# avr3.net
KiCad netlist of a schematic drawn in EAGLE
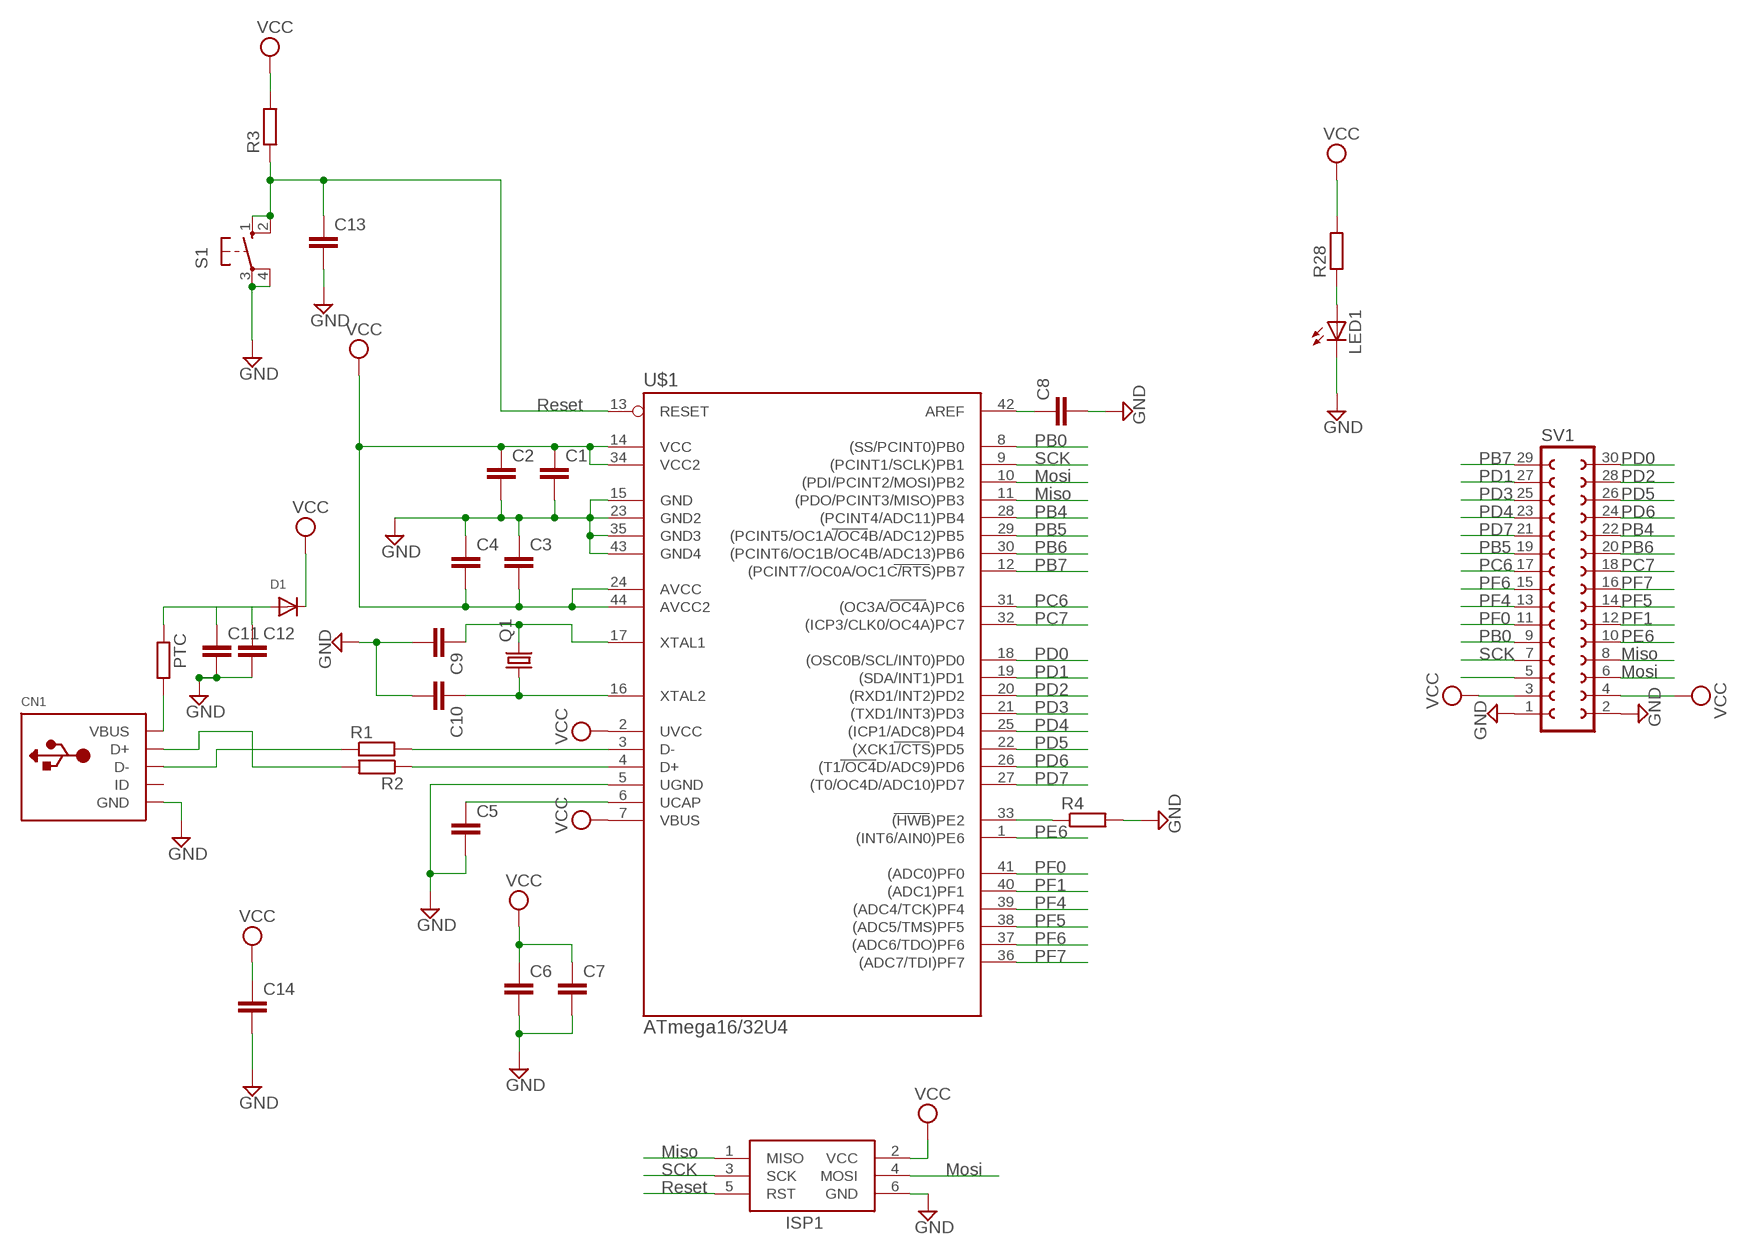
[diagram p0: schematic, sheet 1]

(export (version "E")
  (design (tool "Eeschema 10.0.6"))
  (components
    (comp (ref "C1")
      (value "C-EUC1206")
      (footprint "eagle-import:C1206")
      (libsource (lib "eagle-import") (part "C-EUC1206"))
    )
    (comp (ref "C2")
      (value "C-EUC1206")
      (footprint "eagle-import:C1206")
      (libsource (lib "eagle-import") (part "C-EUC1206"))
    )
    (comp (ref "C3")
      (value "C-EUC1206")
      (footprint "eagle-import:C1206")
      (libsource (lib "eagle-import") (part "C-EUC1206"))
    )
    (comp (ref "C4")
      (value "C-EUC1206")
      (footprint "eagle-import:C1206")
      (libsource (lib "eagle-import") (part "C-EUC1206"))
    )
    (comp (ref "C5")
      (value "C-EUC1206")
      (footprint "eagle-import:C1206")
      (libsource (lib "eagle-import") (part "C-EUC1206"))
    )
    (comp (ref "C6")
      (value "C-EUC1206")
      (footprint "eagle-import:C1206")
      (libsource (lib "eagle-import") (part "C-EUC1206"))
    )
    (comp (ref "C7")
      (value "C-EUC1206")
      (footprint "eagle-import:C1206")
      (libsource (lib "eagle-import") (part "C-EUC1206"))
    )
    (comp (ref "C8")
      (value "C-EUC1206")
      (footprint "eagle-import:C1206")
      (libsource (lib "eagle-import") (part "C-EUC1206"))
    )
    (comp (ref "C9")
      (value "C-EUC1206")
      (footprint "eagle-import:C1206")
      (libsource (lib "eagle-import") (part "C-EUC1206"))
    )
    (comp (ref "C10")
      (value "C-EUC1206")
      (footprint "eagle-import:C1206")
      (libsource (lib "eagle-import") (part "C-EUC1206"))
    )
    (comp (ref "C11")
      (value "C-EUC1206")
      (footprint "eagle-import:C1206")
      (libsource (lib "eagle-import") (part "C-EUC1206"))
    )
    (comp (ref "C12")
      (value "C-EUC1206")
      (footprint "eagle-import:C1206")
      (libsource (lib "eagle-import") (part "C-EUC1206"))
    )
    (comp (ref "C13")
      (value "C-EUC1206")
      (footprint "eagle-import:C1206")
      (libsource (lib "eagle-import") (part "C-EUC1206"))
    )
    (comp (ref "C14")
      (value "C-EUC1206")
      (footprint "eagle-import:C1206")
      (libsource (lib "eagle-import") (part "C-EUC1206"))
    )
    (comp (ref "CN1")
      (value "USBMINIB")
      (footprint "eagle-import:USB-MINIB")
      (libsource (lib "eagle-import") (part "USBMINIB"))
    )
    (comp (ref "D1")
      (value "DIODESOD-123")
      (footprint "eagle-import:SOD-123")
      (libsource (lib "eagle-import") (part "DIODESOD-123"))
    )
    (comp (ref "ISP1")
      (value "AVRISP-6")
      (footprint "eagle-import:AVRISP")
      (libsource (lib "eagle-import") (part "AVRISP-6"))
    )
    (comp (ref "LED1")
      (value "LEDCHIPLED_1206")
      (footprint "eagle-import:CHIPLED_1206")
      (libsource (lib "eagle-import") (part "LEDCHIPLED_1206"))
    )
    (comp (ref "PTC")
      (value "R-EU_R1206")
      (footprint "eagle-import:R1206")
      (libsource (lib "eagle-import") (part "R-EU_R1206"))
    )
    (comp (ref "Q1")
      (value "CRYSTALHC49UP")
      (footprint "eagle-import:HC49UP")
      (fields (field (name "OC_FARNELL") "unknown") (field (name "OC_NEWARK") "unknown"))
      (libsource (lib "eagle-import") (part "CRYSTALHC49UP"))
    )
    (comp (ref "R1")
      (value "R-EU_R1206")
      (footprint "eagle-import:R1206")
      (libsource (lib "eagle-import") (part "R-EU_R1206"))
    )
    (comp (ref "R2")
      (value "R-EU_R1206")
      (footprint "eagle-import:R1206")
      (libsource (lib "eagle-import") (part "R-EU_R1206"))
    )
    (comp (ref "R3")
      (value "R-EU_R1206")
      (footprint "eagle-import:R1206")
      (libsource (lib "eagle-import") (part "R-EU_R1206"))
    )
    (comp (ref "R4")
      (value "R-EU_R1206")
      (footprint "eagle-import:R1206")
      (libsource (lib "eagle-import") (part "R-EU_R1206"))
    )
    (comp (ref "R28")
      (value "R-EU_R1206")
      (footprint "eagle-import:R1206")
      (libsource (lib "eagle-import") (part "R-EU_R1206"))
    )
    (comp (ref "S1")
      (value "10-XX")
      (footprint "eagle-import:B3F-10XX")
      (fields (field (name "MPN") "B3F-1000"))
      (libsource (lib "eagle-import") (part "10-XX"))
    )
    (comp (ref "SV1")
      (value "FE15-2")
      (footprint "eagle-import:FE15-2")
      (libsource (lib "eagle-import") (part "FE15-2"))
    )
    (comp (ref "U$1")
      (value "ATmega16/32U4")
      (footprint "eagle-import:TQFP44")
      (libsource (lib "eagle-import") (part "ATMEGA32U4-AU"))
    )
  )
  (nets
    (net (code "1") (name "/MISO") (class "Default")
      (node (ref "ISP1") (pin "1") (pinfunction "MISO_1") (pintype "input"))
      (node (ref "SV1") (pin "8") (pinfunction "8_8") (pintype "passive"))
      (node (ref "U$1") (pin "11") (pinfunction "(PDO/PCINT3/MISO)PB3_11") (pintype "bidirectional"))
    )
    (net (code "2") (name "/MOSI") (class "Default")
      (node (ref "ISP1") (pin "4") (pinfunction "MOSI_4") (pintype "output"))
      (node (ref "SV1") (pin "6") (pinfunction "6_6") (pintype "passive"))
      (node (ref "U$1") (pin "10") (pinfunction "(PDI/PCINT2/MOSI)PB2_10") (pintype "bidirectional"))
    )
    (net (code "3") (name "/PB0") (class "Default")
      (node (ref "SV1") (pin "9") (pinfunction "9_9") (pintype "passive"))
      (node (ref "U$1") (pin "8") (pinfunction "(SS/PCINT0)PB0_8") (pintype "bidirectional"))
    )
    (net (code "4") (name "/PB4") (class "Default")
      (node (ref "SV1") (pin "22") (pinfunction "22_22") (pintype "passive"))
      (node (ref "U$1") (pin "28") (pinfunction "(PCINT4/ADC11)PB4_28") (pintype "bidirectional"))
    )
    (net (code "5") (name "/PB5") (class "Default")
      (node (ref "SV1") (pin "19") (pinfunction "19_19") (pintype "passive"))
      (node (ref "U$1") (pin "29") (pinfunction "(PCINT5/OC1A/OC4B/ADC12)PB5_29") (pintype "bidirectional"))
    )
    (net (code "6") (name "/PB6") (class "Default")
      (node (ref "SV1") (pin "20") (pinfunction "20_20") (pintype "passive"))
      (node (ref "U$1") (pin "30") (pinfunction "(PCINT6/OC1B/OC4B/ADC13)PB6_30") (pintype "bidirectional"))
    )
    (net (code "7") (name "/PB7") (class "Default")
      (node (ref "SV1") (pin "29") (pinfunction "29_29") (pintype "passive"))
      (node (ref "U$1") (pin "12") (pinfunction "(PCINT7/OC0A/OC1C/RTS)PB7_12") (pintype "bidirectional"))
    )
    (net (code "8") (name "/PC6") (class "Default")
      (node (ref "SV1") (pin "17") (pinfunction "17_17") (pintype "passive"))
      (node (ref "U$1") (pin "31") (pinfunction "(OC3A/OC4A)PC6_31") (pintype "bidirectional"))
    )
    (net (code "9") (name "/PC7") (class "Default")
      (node (ref "SV1") (pin "18") (pinfunction "18_18") (pintype "passive"))
      (node (ref "U$1") (pin "32") (pinfunction "(ICP3/CLK0/OC4A)PC7_32") (pintype "bidirectional"))
    )
    (net (code "10") (name "/PD0") (class "Default")
      (node (ref "SV1") (pin "30") (pinfunction "30_30") (pintype "passive"))
      (node (ref "U$1") (pin "18") (pinfunction "(OSC0B/SCL/INT0)PD0_18") (pintype "bidirectional"))
    )
    (net (code "11") (name "/PD1") (class "Default")
      (node (ref "SV1") (pin "27") (pinfunction "27_27") (pintype "passive"))
      (node (ref "U$1") (pin "19") (pinfunction "(SDA/INT1)PD1_19") (pintype "bidirectional"))
    )
    (net (code "12") (name "/PD2") (class "Default")
      (node (ref "SV1") (pin "28") (pinfunction "28_28") (pintype "passive"))
      (node (ref "U$1") (pin "20") (pinfunction "(RXD1/INT2)PD2_20") (pintype "bidirectional"))
    )
    (net (code "13") (name "/PD3") (class "Default")
      (node (ref "SV1") (pin "25") (pinfunction "25_25") (pintype "passive"))
      (node (ref "U$1") (pin "21") (pinfunction "(TXD1/INT3)PD3_21") (pintype "bidirectional"))
    )
    (net (code "14") (name "/PD4") (class "Default")
      (node (ref "SV1") (pin "23") (pinfunction "23_23") (pintype "passive"))
      (node (ref "U$1") (pin "25") (pinfunction "(ICP1/ADC8)PD4_25") (pintype "bidirectional"))
    )
    (net (code "15") (name "/PD5") (class "Default")
      (node (ref "SV1") (pin "26") (pinfunction "26_26") (pintype "passive"))
      (node (ref "U$1") (pin "22") (pinfunction "(XCK1/CTS)PD5_22") (pintype "bidirectional"))
    )
    (net (code "16") (name "/PD6") (class "Default")
      (node (ref "SV1") (pin "24") (pinfunction "24_24") (pintype "passive"))
      (node (ref "U$1") (pin "26") (pinfunction "(T1/OC4D/ADC9)PD6_26") (pintype "bidirectional"))
    )
    (net (code "17") (name "/PD7") (class "Default")
      (node (ref "SV1") (pin "21") (pinfunction "21_21") (pintype "passive"))
      (node (ref "U$1") (pin "27") (pinfunction "(T0/OC4D/ADC10)PD7_27") (pintype "bidirectional"))
    )
    (net (code "18") (name "/PE6") (class "Default")
      (node (ref "SV1") (pin "10") (pinfunction "10_10") (pintype "passive"))
      (node (ref "U$1") (pin "1") (pinfunction "(INT6/AIN0)PE6_1") (pintype "bidirectional"))
    )
    (net (code "19") (name "/PF0") (class "Default")
      (node (ref "SV1") (pin "11") (pinfunction "11_11") (pintype "passive"))
      (node (ref "U$1") (pin "41") (pinfunction "(ADC0)PF0_41") (pintype "bidirectional"))
    )
    (net (code "20") (name "/PF1") (class "Default")
      (node (ref "SV1") (pin "12") (pinfunction "12_12") (pintype "passive"))
      (node (ref "U$1") (pin "40") (pinfunction "(ADC1)PF1_40") (pintype "bidirectional"))
    )
    (net (code "21") (name "/PF4") (class "Default")
      (node (ref "SV1") (pin "13") (pinfunction "13_13") (pintype "passive"))
      (node (ref "U$1") (pin "39") (pinfunction "(ADC4/TCK)PF4_39") (pintype "bidirectional"))
    )
    (net (code "22") (name "/PF5") (class "Default")
      (node (ref "SV1") (pin "14") (pinfunction "14_14") (pintype "passive"))
      (node (ref "U$1") (pin "38") (pinfunction "(ADC5/TMS)PF5_38") (pintype "bidirectional"))
    )
    (net (code "23") (name "/PF6") (class "Default")
      (node (ref "SV1") (pin "15") (pinfunction "15_15") (pintype "passive"))
      (node (ref "U$1") (pin "37") (pinfunction "(ADC6/TDO)PF6_37") (pintype "bidirectional"))
    )
    (net (code "24") (name "/PF7") (class "Default")
      (node (ref "SV1") (pin "16") (pinfunction "16_16") (pintype "passive"))
      (node (ref "U$1") (pin "36") (pinfunction "(ADC7/TDI)PF7_36") (pintype "bidirectional"))
    )
    (net (code "25") (name "/RESET") (class "Default")
      (node (ref "C13") (pin "1") (pinfunction "1_1") (pintype "passive"))
      (node (ref "ISP1") (pin "5") (pinfunction "RST_5") (pintype "output"))
      (node (ref "R3") (pin "1") (pinfunction "1_1") (pintype "passive"))
      (node (ref "S1") (pin "1") (pinfunction "S_1") (pintype "passive"))
      (node (ref "S1") (pin "2") (pinfunction "S1_2") (pintype "passive"))
      (node (ref "U$1") (pin "13") (pinfunction "RESET_13") (pintype "bidirectional"))
    )
    (net (code "26") (name "/SCK") (class "Default")
      (node (ref "ISP1") (pin "3") (pinfunction "SCK_3") (pintype "output"))
      (node (ref "SV1") (pin "7") (pinfunction "7_7") (pintype "passive"))
      (node (ref "U$1") (pin "9") (pinfunction "(PCINT1/SCLK)PB1_9") (pintype "bidirectional"))
    )
    (net (code "27") (name "GND") (class "Default")
      (node (ref "C1") (pin "2") (pinfunction "2_2") (pintype "passive"))
      (node (ref "C10") (pin "2") (pinfunction "2_2") (pintype "passive"))
      (node (ref "C11") (pin "2") (pinfunction "2_2") (pintype "passive"))
      (node (ref "C12") (pin "2") (pinfunction "2_2") (pintype "passive"))
      (node (ref "C13") (pin "2") (pinfunction "2_2") (pintype "passive"))
      (node (ref "C14") (pin "2") (pinfunction "2_2") (pintype "passive"))
      (node (ref "C2") (pin "2") (pinfunction "2_2") (pintype "passive"))
      (node (ref "C3") (pin "1") (pinfunction "1_1") (pintype "passive"))
      (node (ref "C4") (pin "1") (pinfunction "1_1") (pintype "passive"))
      (node (ref "C5") (pin "2") (pinfunction "2_2") (pintype "passive"))
      (node (ref "C6") (pin "2") (pinfunction "2_2") (pintype "passive"))
      (node (ref "C7") (pin "2") (pinfunction "2_2") (pintype "passive"))
      (node (ref "C8") (pin "2") (pinfunction "2_2") (pintype "passive"))
      (node (ref "C9") (pin "2") (pinfunction "2_2") (pintype "passive"))
      (node (ref "CN1") (pin "GND") (pinfunction "GND_GND") (pintype "power_in"))
      (node (ref "ISP1") (pin "6") (pinfunction "GND_6") (pintype "power_in"))
      (node (ref "LED1") (pin "C") (pinfunction "C_C") (pintype "passive"))
      (node (ref "R4") (pin "2") (pinfunction "2_2") (pintype "passive"))
      (node (ref "S1") (pin "3") (pinfunction "P_3") (pintype "passive"))
      (node (ref "S1") (pin "4") (pinfunction "P1_4") (pintype "passive"))
      (node (ref "SV1") (pin "1") (pinfunction "1_1") (pintype "passive"))
      (node (ref "SV1") (pin "2") (pinfunction "2_2") (pintype "passive"))
      (node (ref "U$1") (pin "15") (pinfunction "GND_15") (pintype "bidirectional"))
      (node (ref "U$1") (pin "23") (pinfunction "GND2_23") (pintype "bidirectional"))
      (node (ref "U$1") (pin "35") (pinfunction "GND3_35") (pintype "bidirectional"))
      (node (ref "U$1") (pin "43") (pinfunction "GND4_43") (pintype "bidirectional"))
      (node (ref "U$1") (pin "5") (pinfunction "UGND_5") (pintype "bidirectional"))
    )
    (net (code "28") (name "Net-(C11-Pad1)") (class "Default")
      (node (ref "C11") (pin "1") (pinfunction "1_1") (pintype "passive"))
      (node (ref "C12") (pin "1") (pinfunction "1_1") (pintype "passive"))
      (node (ref "D1") (pin "A") (pinfunction "A_A") (pintype "passive"))
      (node (ref "PTC") (pin "1") (pinfunction "1_1") (pintype "passive"))
    )
    (net (code "29") (name "Net-(CN1-PadD+)") (class "Default")
      (node (ref "CN1") (pin "D+") (pinfunction "D+_D+") (pintype "bidirectional"))
      (node (ref "R2") (pin "2") (pinfunction "2_2") (pintype "passive"))
    )
    (net (code "30") (name "Net-(CN1-PadD-)") (class "Default")
      (node (ref "CN1") (pin "D-") (pinfunction "D-_D-") (pintype "bidirectional"))
      (node (ref "R1") (pin "1") (pinfunction "1_1") (pintype "passive"))
    )
    (net (code "31") (name "Net-(CN1-PadVBUS)") (class "Default")
      (node (ref "CN1") (pin "VBUS") (pinfunction "VBUS_VBUS") (pintype "power_in"))
      (node (ref "PTC") (pin "2") (pinfunction "2_2") (pintype "passive"))
    )
    (net (code "32") (name "Net-(LED1-PadA)") (class "Default")
      (node (ref "LED1") (pin "A") (pinfunction "A_A") (pintype "passive"))
      (node (ref "R28") (pin "1") (pinfunction "1_1") (pintype "passive"))
    )
    (net (code "33") (name "Net-(U$1-(HWB)PE2)") (class "Default")
      (node (ref "R4") (pin "1") (pinfunction "1_1") (pintype "passive"))
      (node (ref "U$1") (pin "33") (pinfunction "(HWB)PE2_33") (pintype "bidirectional"))
    )
    (net (code "34") (name "Net-(U$1-AREF)") (class "Default")
      (node (ref "C8") (pin "1") (pinfunction "1_1") (pintype "passive"))
      (node (ref "U$1") (pin "42") (pinfunction "AREF_42") (pintype "bidirectional"))
    )
    (net (code "35") (name "Net-(U$1-D+)") (class "Default")
      (node (ref "R2") (pin "1") (pinfunction "1_1") (pintype "passive"))
      (node (ref "U$1") (pin "4") (pinfunction "D+_4") (pintype "bidirectional"))
    )
    (net (code "36") (name "Net-(U$1-D-)") (class "Default")
      (node (ref "R1") (pin "2") (pinfunction "2_2") (pintype "passive"))
      (node (ref "U$1") (pin "3") (pinfunction "D-_3") (pintype "bidirectional"))
    )
    (net (code "37") (name "Net-(U$1-UCAP)") (class "Default")
      (node (ref "C5") (pin "1") (pinfunction "1_1") (pintype "passive"))
      (node (ref "U$1") (pin "6") (pinfunction "UCAP_6") (pintype "bidirectional"))
    )
    (net (code "38") (name "Net-(U$1-XTAL1)") (class "Default")
      (node (ref "C9") (pin "1") (pinfunction "1_1") (pintype "passive"))
      (node (ref "Q1") (pin "2") (pinfunction "2_2") (pintype "passive"))
      (node (ref "U$1") (pin "17") (pinfunction "XTAL1_17") (pintype "bidirectional"))
    )
    (net (code "39") (name "Net-(U$1-XTAL2)") (class "Default")
      (node (ref "C10") (pin "1") (pinfunction "1_1") (pintype "passive"))
      (node (ref "Q1") (pin "1") (pinfunction "1_1") (pintype "passive"))
      (node (ref "U$1") (pin "16") (pinfunction "XTAL2_16") (pintype "bidirectional"))
    )
    (net (code "40") (name "VCC") (class "Default")
      (node (ref "C1") (pin "1") (pinfunction "1_1") (pintype "passive"))
      (node (ref "C14") (pin "1") (pinfunction "1_1") (pintype "passive"))
      (node (ref "C2") (pin "1") (pinfunction "1_1") (pintype "passive"))
      (node (ref "C3") (pin "2") (pinfunction "2_2") (pintype "passive"))
      (node (ref "C4") (pin "2") (pinfunction "2_2") (pintype "passive"))
      (node (ref "C6") (pin "1") (pinfunction "1_1") (pintype "passive"))
      (node (ref "C7") (pin "1") (pinfunction "1_1") (pintype "passive"))
      (node (ref "D1") (pin "C") (pinfunction "C_C") (pintype "passive"))
      (node (ref "ISP1") (pin "2") (pinfunction "VCC_2") (pintype "power_in"))
      (node (ref "R28") (pin "2") (pinfunction "2_2") (pintype "passive"))
      (node (ref "R3") (pin "2") (pinfunction "2_2") (pintype "passive"))
      (node (ref "SV1") (pin "3") (pinfunction "3_3") (pintype "passive"))
      (node (ref "SV1") (pin "4") (pinfunction "4_4") (pintype "passive"))
      (node (ref "U$1") (pin "14") (pinfunction "VCC_14") (pintype "bidirectional"))
      (node (ref "U$1") (pin "2") (pinfunction "UVCC_2") (pintype "bidirectional"))
      (node (ref "U$1") (pin "24") (pinfunction "AVCC_24") (pintype "bidirectional"))
      (node (ref "U$1") (pin "34") (pinfunction "VCC2_34") (pintype "bidirectional"))
      (node (ref "U$1") (pin "44") (pinfunction "AVCC2_44") (pintype "bidirectional"))
      (node (ref "U$1") (pin "7") (pinfunction "VBUS_7") (pintype "bidirectional"))
    )
    (net (code "41") (name "unconnected-(CN1-PadID)") (class "Default")
      (node (ref "CN1") (pin "ID") (pinfunction "ID_ID") (pintype "bidirectional"))
    )
    (net (code "42") (name "unconnected-(SV1-Pad5)") (class "Default")
      (node (ref "SV1") (pin "5") (pinfunction "5_5") (pintype "passive"))
    )
  )
)
